# motorDriver.net
KiCad netlist of a schematic drawn in EAGLE
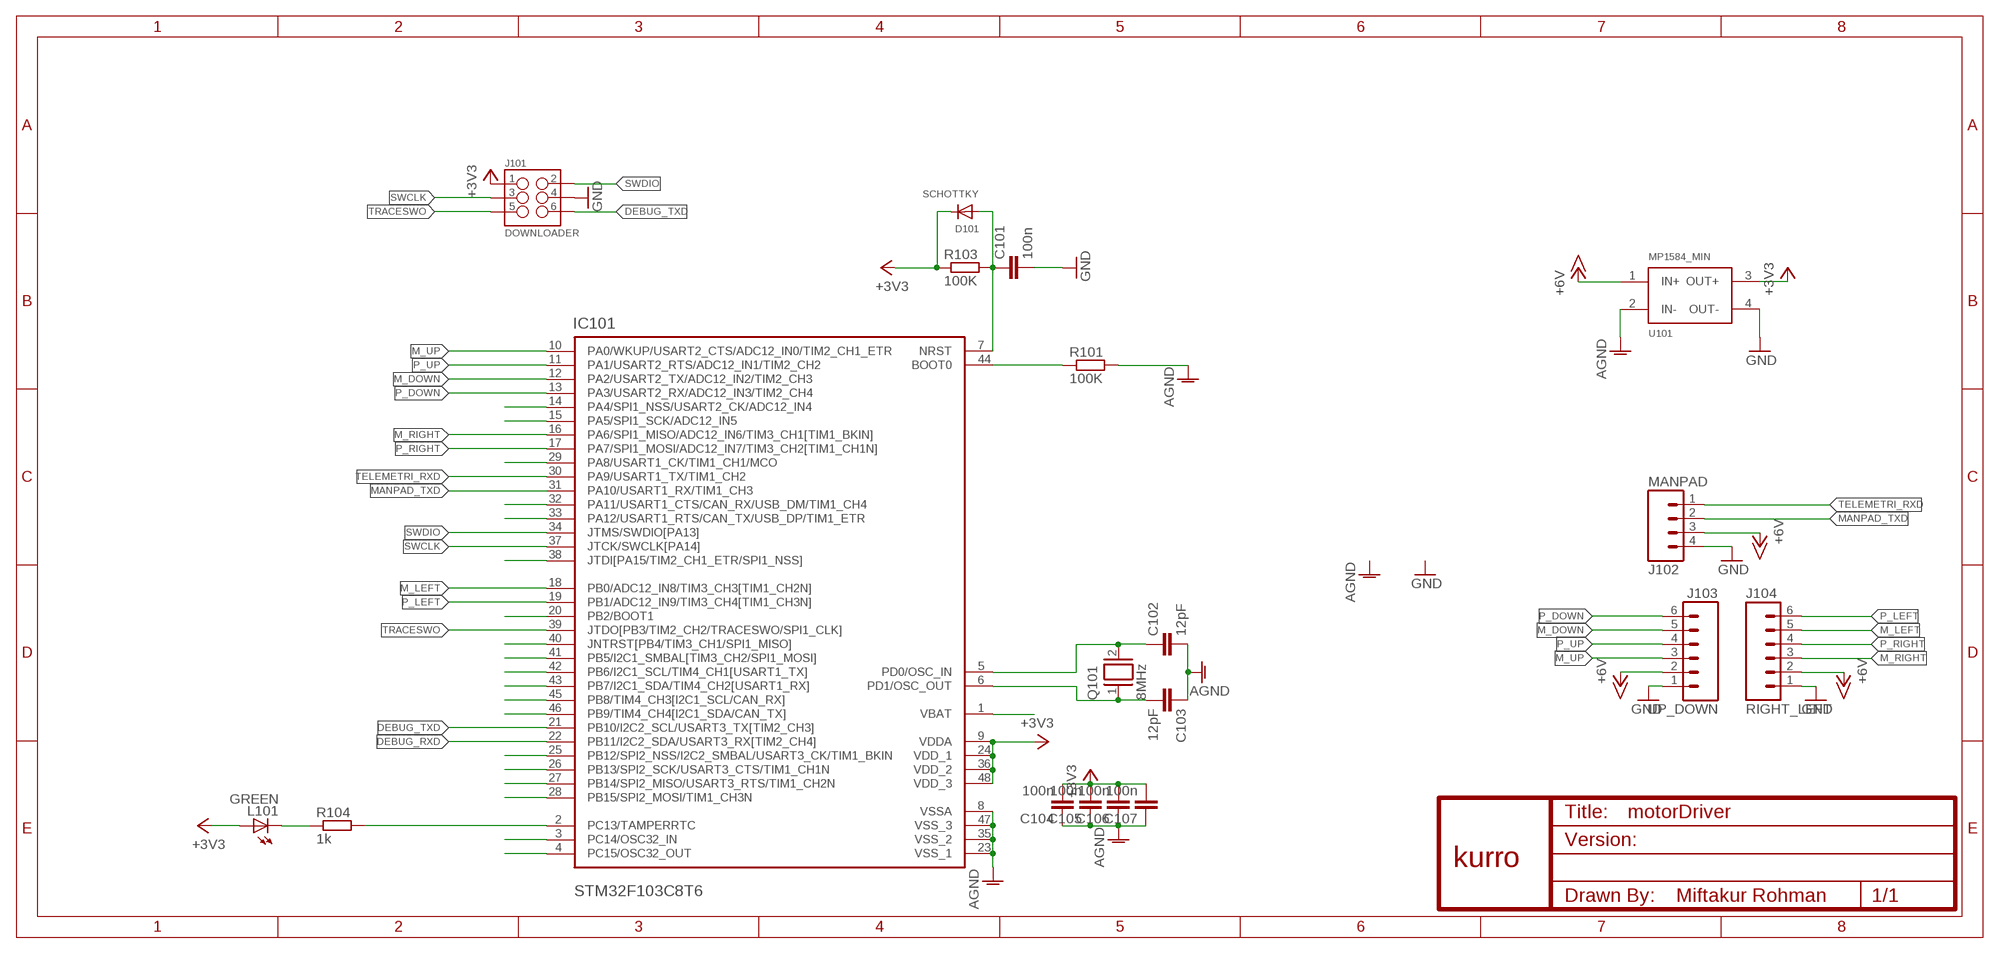
[diagram p0: schematic, sheet 1]

(export (version "E")
  (design (tool "Eeschema 10.0.6"))
  (components
    (comp (ref "C101")
      (value "100n")
      (footprint "eagle-import:C0603")
      (libsource (lib "eagle-import") (part "C-EUC0603"))
    )
    (comp (ref "C102")
      (value "12pF")
      (footprint "eagle-import:C0603")
      (libsource (lib "eagle-import") (part "C-EUC0603"))
    )
    (comp (ref "C103")
      (value "12pF")
      (footprint "eagle-import:C0603")
      (libsource (lib "eagle-import") (part "C-EUC0603"))
    )
    (comp (ref "C104")
      (value "100n")
      (footprint "eagle-import:C0603")
      (libsource (lib "eagle-import") (part "C-EUC0603"))
    )
    (comp (ref "C105")
      (value "100n")
      (footprint "eagle-import:C0603")
      (libsource (lib "eagle-import") (part "C-EUC0603"))
    )
    (comp (ref "C106")
      (value "100n")
      (footprint "eagle-import:C0603")
      (libsource (lib "eagle-import") (part "C-EUC0603"))
    )
    (comp (ref "C107")
      (value "100n")
      (footprint "eagle-import:C0603")
      (libsource (lib "eagle-import") (part "C-EUC0603"))
    )
    (comp (ref "D101")
      (value "SCHOTTKY")
      (footprint "eagle-import:SOD-323F")
      (libsource (lib "eagle-import") (part "DIODESOD-323F"))
    )
    (comp (ref "IC101")
      (value "STM32F103C8T6")
      (footprint "eagle-import:QFP50P900X900X160-48N")
      (fields (field (name "MPN") "STM32F103CBT6"))
      (libsource (lib "eagle-import") (part "STM32F103C8T6"))
    )
    (comp (ref "J101")
      (value "DOWNLOADER")
      (footprint "eagle-import:2X3_SMD")
      (libsource (lib "eagle-import") (part "M03X2"))
    )
    (comp (ref "J102")
      (value "MANPAD")
      (footprint "eagle-import:XH-4-VERT-SMD")
      (libsource (lib "eagle-import") (part "M04-XH-VERT-SMD"))
    )
    (comp (ref "J103")
      (value "UP_DOWN")
      (footprint "eagle-import:XH-6-VERT-SMD")
      (libsource (lib "eagle-import") (part "M06-XH-VERT-SMD"))
    )
    (comp (ref "J104")
      (value "RIGHT_LEFT")
      (footprint "eagle-import:XH-6-VERT-SMD")
      (libsource (lib "eagle-import") (part "M06-XH-VERT-SMD"))
    )
    (comp (ref "L101")
      (value "GREEN")
      (footprint "eagle-import:CHIP-LED0805")
      (libsource (lib "eagle-import") (part "LEDCHIP-LED0805"))
    )
    (comp (ref "Q101")
      (value "8MHz")
      (footprint "eagle-import:QS")
      (libsource (lib "eagle-import") (part "XTAL/S"))
    )
    (comp (ref "R101")
      (value "100K")
      (footprint "eagle-import:R0603")
      (libsource (lib "eagle-import") (part "R-EU_R0603"))
    )
    (comp (ref "R103")
      (value "100K")
      (footprint "eagle-import:R0603")
      (libsource (lib "eagle-import") (part "R-EU_R0603"))
    )
    (comp (ref "R104")
      (value "1k")
      (footprint "eagle-import:R0603")
      (libsource (lib "eagle-import") (part "R-EU_R0603"))
    )
    (comp (ref "U$1")
      (value "KURRO_FOOTPRINT")
      (footprint "eagle-import:KURRO-LOGO")
      (libsource (lib "eagle-import") (part "KURRO_FOOTPRINT"))
    )
    (comp (ref "U101")
      (value "MP1584_MIN")
      (footprint "eagle-import:MP1584_MIN")
      (libsource (lib "eagle-import") (part "MP1584_MIN"))
    )
  )
  (nets
    (net (code "1") (name "+3V3") (class "Default")
      (node (ref "C104") (pin "2") (pinfunction "2_2") (pintype "passive"))
      (node (ref "C105") (pin "2") (pinfunction "2_2") (pintype "passive"))
      (node (ref "C106") (pin "2") (pinfunction "2_2") (pintype "passive"))
      (node (ref "C107") (pin "2") (pinfunction "2_2") (pintype "passive"))
      (node (ref "D101") (pin "C") (pinfunction "C_C") (pintype "passive"))
      (node (ref "IC101") (pin "24") (pinfunction "VDD_1_24") (pintype "bidirectional"))
      (node (ref "IC101") (pin "36") (pinfunction "VDD_2_36") (pintype "power_in"))
      (node (ref "IC101") (pin "48") (pinfunction "VDD_3_48") (pintype "power_in"))
      (node (ref "IC101") (pin "9") (pinfunction "VDDA_9") (pintype "power_in"))
      (node (ref "J101") (pin "1") (pinfunction "1_1") (pintype "bidirectional"))
      (node (ref "L101") (pin "A") (pinfunction "A_A") (pintype "passive"))
      (node (ref "R103") (pin "1") (pinfunction "1_1") (pintype "passive"))
      (node (ref "U101") (pin "3") (pinfunction "OUT+_3") (pintype "passive"))
    )
    (net (code "2") (name "+6V") (class "Default")
      (node (ref "J102") (pin "3") (pinfunction "3_3") (pintype "passive"))
      (node (ref "J103") (pin "2") (pinfunction "2_2") (pintype "passive"))
      (node (ref "J104") (pin "2") (pinfunction "2_2") (pintype "passive"))
      (node (ref "U101") (pin "1") (pinfunction "IN+_1") (pintype "input"))
    )
    (net (code "3") (name "AGND") (class "Default")
      (node (ref "C102") (pin "2") (pinfunction "2_2") (pintype "passive"))
      (node (ref "C103") (pin "1") (pinfunction "1_1") (pintype "passive"))
      (node (ref "C104") (pin "1") (pinfunction "1_1") (pintype "passive"))
      (node (ref "C105") (pin "1") (pinfunction "1_1") (pintype "passive"))
      (node (ref "C106") (pin "1") (pinfunction "1_1") (pintype "passive"))
      (node (ref "C107") (pin "1") (pinfunction "1_1") (pintype "passive"))
      (node (ref "IC101") (pin "23") (pinfunction "VSS_1_23") (pintype "bidirectional"))
      (node (ref "IC101") (pin "35") (pinfunction "VSS_2_35") (pintype "passive"))
      (node (ref "IC101") (pin "47") (pinfunction "VSS_3_47") (pintype "passive"))
      (node (ref "IC101") (pin "8") (pinfunction "VSSA_8") (pintype "passive"))
      (node (ref "R101") (pin "2") (pinfunction "2_2") (pintype "passive"))
      (node (ref "U101") (pin "2") (pinfunction "IN-_2") (pintype "passive"))
    )
    (net (code "4") (name "DEBUG_RXD") (class "Default")
      (node (ref "IC101") (pin "22") (pinfunction "PB11/I2C2_SDA/USART3_RX[TIM2_CH4]_22") (pintype "bidirectional"))
    )
    (net (code "5") (name "DEBUG_TXD") (class "Default")
      (node (ref "IC101") (pin "21") (pinfunction "PB10/I2C2_SCL/USART3_TX[TIM2_CH3]_21") (pintype "bidirectional"))
      (node (ref "J101") (pin "6") (pinfunction "6_6") (pintype "bidirectional"))
    )
    (net (code "6") (name "GND") (class "Default")
      (node (ref "C101") (pin "2") (pinfunction "2_2") (pintype "passive"))
      (node (ref "J101") (pin "4") (pinfunction "4_4") (pintype "bidirectional"))
      (node (ref "J102") (pin "4") (pinfunction "4_4") (pintype "passive"))
      (node (ref "J103") (pin "1") (pinfunction "1_1") (pintype "passive"))
      (node (ref "J104") (pin "1") (pinfunction "1_1") (pintype "passive"))
      (node (ref "U101") (pin "4") (pinfunction "OUT-_4") (pintype "passive"))
    )
    (net (code "7") (name "MANPAD_TXD") (class "Default")
      (node (ref "IC101") (pin "31") (pinfunction "PA10/USART1_RX/TIM1_CH3_31") (pintype "bidirectional"))
      (node (ref "J102") (pin "2") (pinfunction "2_2") (pintype "passive"))
    )
    (net (code "8") (name "M_DOWN") (class "Default")
      (node (ref "IC101") (pin "12") (pinfunction "PA2/USART2_TX/ADC12_IN2/TIM2_CH3_12") (pintype "bidirectional"))
      (node (ref "J103") (pin "5") (pinfunction "5_5") (pintype "passive"))
    )
    (net (code "9") (name "M_LEFT") (class "Default")
      (node (ref "IC101") (pin "18") (pinfunction "PB0/ADC12_IN8/TIM3_CH3[TIM1_CH2N]_18") (pintype "bidirectional"))
      (node (ref "J104") (pin "5") (pinfunction "5_5") (pintype "passive"))
    )
    (net (code "10") (name "M_RIGHT") (class "Default")
      (node (ref "IC101") (pin "16") (pinfunction "PA6/SPI1_MISO/ADC12_IN6/TIM3_CH1[TIM1_BKIN]_16") (pintype "bidirectional"))
      (node (ref "J104") (pin "3") (pinfunction "3_3") (pintype "passive"))
    )
    (net (code "11") (name "M_UP") (class "Default")
      (node (ref "IC101") (pin "10") (pinfunction "PA0/WKUP/USART2_CTS/ADC12_IN0/TIM2_CH1_ETR_10") (pintype "bidirectional"))
      (node (ref "J103") (pin "3") (pinfunction "3_3") (pintype "passive"))
    )
    (net (code "12") (name "Net-(IC101-BOOT0)") (class "Default")
      (node (ref "IC101") (pin "44") (pinfunction "BOOT0_44") (pintype "bidirectional"))
      (node (ref "R101") (pin "1") (pinfunction "1_1") (pintype "passive"))
    )
    (net (code "13") (name "Net-(IC101-NRST)") (class "Default")
      (node (ref "C101") (pin "1") (pinfunction "1_1") (pintype "passive"))
      (node (ref "D101") (pin "A") (pinfunction "A_A") (pintype "passive"))
      (node (ref "IC101") (pin "7") (pinfunction "NRST_7") (pintype "bidirectional"))
      (node (ref "R103") (pin "2") (pinfunction "2_2") (pintype "passive"))
    )
    (net (code "14") (name "Net-(IC101-PC13{slash}TAMPERRTC)") (class "Default")
      (node (ref "IC101") (pin "2") (pinfunction "PC13/TAMPERRTC_2") (pintype "bidirectional"))
      (node (ref "R104") (pin "2") (pinfunction "2_2") (pintype "passive"))
    )
    (net (code "15") (name "Net-(IC101-PD0{slash}OSC_IN)") (class "Default")
      (node (ref "C102") (pin "1") (pinfunction "1_1") (pintype "passive"))
      (node (ref "IC101") (pin "5") (pinfunction "PD0/OSC_IN_5") (pintype "bidirectional"))
      (node (ref "Q101") (pin "2") (pinfunction "2_2") (pintype "passive"))
    )
    (net (code "16") (name "Net-(IC101-PD1{slash}OSC_OUT)") (class "Default")
      (node (ref "C103") (pin "2") (pinfunction "2_2") (pintype "passive"))
      (node (ref "IC101") (pin "6") (pinfunction "PD1/OSC_OUT_6") (pintype "bidirectional"))
      (node (ref "Q101") (pin "1") (pinfunction "1_1") (pintype "passive"))
    )
    (net (code "17") (name "Net-(L101-PadC)") (class "Default")
      (node (ref "L101") (pin "C") (pinfunction "C_C") (pintype "passive"))
      (node (ref "R104") (pin "1") (pinfunction "1_1") (pintype "passive"))
    )
    (net (code "18") (name "P_DOWN") (class "Default")
      (node (ref "IC101") (pin "13") (pinfunction "PA3/USART2_RX/ADC12_IN3/TIM2_CH4_13") (pintype "bidirectional"))
      (node (ref "J103") (pin "6") (pinfunction "6_6") (pintype "passive"))
    )
    (net (code "19") (name "P_LEFT") (class "Default")
      (node (ref "IC101") (pin "19") (pinfunction "PB1/ADC12_IN9/TIM3_CH4[TIM1_CH3N]_19") (pintype "bidirectional"))
      (node (ref "J104") (pin "6") (pinfunction "6_6") (pintype "passive"))
    )
    (net (code "20") (name "P_RIGHT") (class "Default")
      (node (ref "IC101") (pin "17") (pinfunction "PA7/SPI1_MOSI/ADC12_IN7/TIM3_CH2[TIM1_CH1N]_17") (pintype "bidirectional"))
      (node (ref "J104") (pin "4") (pinfunction "4_4") (pintype "passive"))
    )
    (net (code "21") (name "P_UP") (class "Default")
      (node (ref "IC101") (pin "11") (pinfunction "PA1/USART2_RTS/ADC12_IN1/TIM2_CH2_11") (pintype "bidirectional"))
      (node (ref "J103") (pin "4") (pinfunction "4_4") (pintype "passive"))
    )
    (net (code "22") (name "SWCLK") (class "Default")
      (node (ref "IC101") (pin "37") (pinfunction "JTCK/SWCLK[PA14]_37") (pintype "bidirectional"))
      (node (ref "J101") (pin "3") (pinfunction "3_3") (pintype "bidirectional"))
    )
    (net (code "23") (name "SWDIO") (class "Default")
      (node (ref "IC101") (pin "34") (pinfunction "JTMS/SWDIO[PA13]_34") (pintype "bidirectional"))
      (node (ref "J101") (pin "2") (pinfunction "2_2") (pintype "bidirectional"))
    )
    (net (code "24") (name "TELEMETRI_RXD") (class "Default")
      (node (ref "IC101") (pin "30") (pinfunction "PA9/USART1_TX/TIM1_CH2_30") (pintype "bidirectional"))
      (node (ref "J102") (pin "1") (pinfunction "1_1") (pintype "passive"))
    )
    (net (code "25") (name "TRACESWO") (class "Default")
      (node (ref "IC101") (pin "39") (pinfunction "JTDO[PB3/TIM2_CH2/TRACESWO/SPI1_CLK]_39") (pintype "bidirectional"))
      (node (ref "J101") (pin "5") (pinfunction "5_5") (pintype "bidirectional"))
    )
    (net (code "26") (name "unconnected-(IC101-JNTRST[PB4{slash}TIM3_CH1{slash}SPI1_MISO]-Pad40)") (class "Default")
      (node (ref "IC101") (pin "40") (pinfunction "JNTRST[PB4/TIM3_CH1/SPI1_MISO]_40") (pintype "bidirectional"))
    )
    (net (code "27") (name "unconnected-(IC101-JTDI[PA15{slash}TIM2_CH1_ETR{slash}SPI1_NSS]-Pad38)") (class "Default")
      (node (ref "IC101") (pin "38") (pinfunction "JTDI[PA15/TIM2_CH1_ETR/SPI1_NSS]_38") (pintype "bidirectional"))
    )
    (net (code "28") (name "unconnected-(IC101-PA4{slash}SPI1_NSS{slash}USART2_CK{slash}ADC12_IN4-Pad14)") (class "Default")
      (node (ref "IC101") (pin "14") (pinfunction "PA4/SPI1_NSS/USART2_CK/ADC12_IN4_14") (pintype "bidirectional"))
    )
    (net (code "29") (name "unconnected-(IC101-PA5{slash}SPI1_SCK{slash}ADC12_IN5-Pad15)") (class "Default")
      (node (ref "IC101") (pin "15") (pinfunction "PA5/SPI1_SCK/ADC12_IN5_15") (pintype "bidirectional"))
    )
    (net (code "30") (name "unconnected-(IC101-PA8{slash}USART1_CK{slash}TIM1_CH1{slash}MCO-Pad29)") (class "Default")
      (node (ref "IC101") (pin "29") (pinfunction "PA8/USART1_CK/TIM1_CH1/MCO_29") (pintype "bidirectional"))
    )
    (net (code "31") (name "unconnected-(IC101-PA11{slash}USART1_CTS{slash}CAN_RX{slash}USB_DM{slash}TIM1_CH4-Pad32)") (class "Default")
      (node (ref "IC101") (pin "32") (pinfunction "PA11/USART1_CTS/CAN_RX/USB_DM/TIM1_CH4_32") (pintype "power_in"))
    )
    (net (code "32") (name "unconnected-(IC101-PA12{slash}USART1_RTS{slash}CAN_TX{slash}USB_DP{slash}TIM1_ETR-Pad33)") (class "Default")
      (node (ref "IC101") (pin "33") (pinfunction "PA12/USART1_RTS/CAN_TX/USB_DP/TIM1_ETR_33") (pintype "bidirectional"))
    )
    (net (code "33") (name "unconnected-(IC101-PB2{slash}BOOT1-Pad20)") (class "Default")
      (node (ref "IC101") (pin "20") (pinfunction "PB2/BOOT1_20") (pintype "bidirectional"))
    )
    (net (code "34") (name "unconnected-(IC101-PB5{slash}I2C1_SMBAL[TIM3_CH2{slash}SPI1_MOSI]-Pad41)") (class "Default")
      (node (ref "IC101") (pin "41") (pinfunction "PB5/I2C1_SMBAL[TIM3_CH2/SPI1_MOSI]_41") (pintype "bidirectional"))
    )
    (net (code "35") (name "unconnected-(IC101-PB6{slash}I2C1_SCL{slash}TIM4_CH1[USART1_TX]-Pad42)") (class "Default")
      (node (ref "IC101") (pin "42") (pinfunction "PB6/I2C1_SCL/TIM4_CH1[USART1_TX]_42") (pintype "bidirectional"))
    )
    (net (code "36") (name "unconnected-(IC101-PB7{slash}I2C1_SDA{slash}TIM4_CH2[USART1_RX]-Pad43)") (class "Default")
      (node (ref "IC101") (pin "43") (pinfunction "PB7/I2C1_SDA/TIM4_CH2[USART1_RX]_43") (pintype "bidirectional"))
    )
    (net (code "37") (name "unconnected-(IC101-PB8{slash}TIM4_CH3[I2C1_SCL{slash}CAN_RX]-Pad45)") (class "Default")
      (node (ref "IC101") (pin "45") (pinfunction "PB8/TIM4_CH3[I2C1_SCL/CAN_RX]_45") (pintype "bidirectional"))
    )
    (net (code "38") (name "unconnected-(IC101-PB9{slash}TIM4_CH4[I2C1_SDA{slash}CAN_TX]-Pad46)") (class "Default")
      (node (ref "IC101") (pin "46") (pinfunction "PB9/TIM4_CH4[I2C1_SDA/CAN_TX]_46") (pintype "bidirectional"))
    )
    (net (code "39") (name "unconnected-(IC101-PB12{slash}SPI2_NSS{slash}I2C2_SMBAL{slash}USART3_CK{slash}TIM1_BKIN-Pad25)") (class "Default")
      (node (ref "IC101") (pin "25") (pinfunction "PB12/SPI2_NSS/I2C2_SMBAL/USART3_CK/TIM1_BKIN_25") (pintype "bidirectional"))
    )
    (net (code "40") (name "unconnected-(IC101-PB13{slash}SPI2_SCK{slash}USART3_CTS{slash}TIM1_CH1N-Pad26)") (class "Default")
      (node (ref "IC101") (pin "26") (pinfunction "PB13/SPI2_SCK/USART3_CTS/TIM1_CH1N_26") (pintype "bidirectional"))
    )
    (net (code "41") (name "unconnected-(IC101-PB14{slash}SPI2_MISO{slash}USART3_RTS{slash}TIM1_CH2N-Pad27)") (class "Default")
      (node (ref "IC101") (pin "27") (pinfunction "PB14/SPI2_MISO/USART3_RTS/TIM1_CH2N_27") (pintype "bidirectional"))
    )
    (net (code "42") (name "unconnected-(IC101-PB15{slash}SPI2_MOSI{slash}TIM1_CH3N-Pad28)") (class "Default")
      (node (ref "IC101") (pin "28") (pinfunction "PB15/SPI2_MOSI/TIM1_CH3N_28") (pintype "bidirectional"))
    )
    (net (code "43") (name "unconnected-(IC101-PC14{slash}OSC32_IN-Pad3)") (class "Default")
      (node (ref "IC101") (pin "3") (pinfunction "PC14/OSC32_IN_3") (pintype "bidirectional"))
    )
    (net (code "44") (name "unconnected-(IC101-PC15{slash}OSC32_OUT-Pad4)") (class "Default")
      (node (ref "IC101") (pin "4") (pinfunction "PC15/OSC32_OUT_4") (pintype "bidirectional"))
    )
    (net (code "45") (name "unconnected-(IC101-VBAT-Pad1)") (class "Default")
      (node (ref "IC101") (pin "1") (pinfunction "VBAT_1") (pintype "input"))
    )
  )
)
